# 5_2_switches.net
KiCad netlist of a schematic drawn in Altium Designer
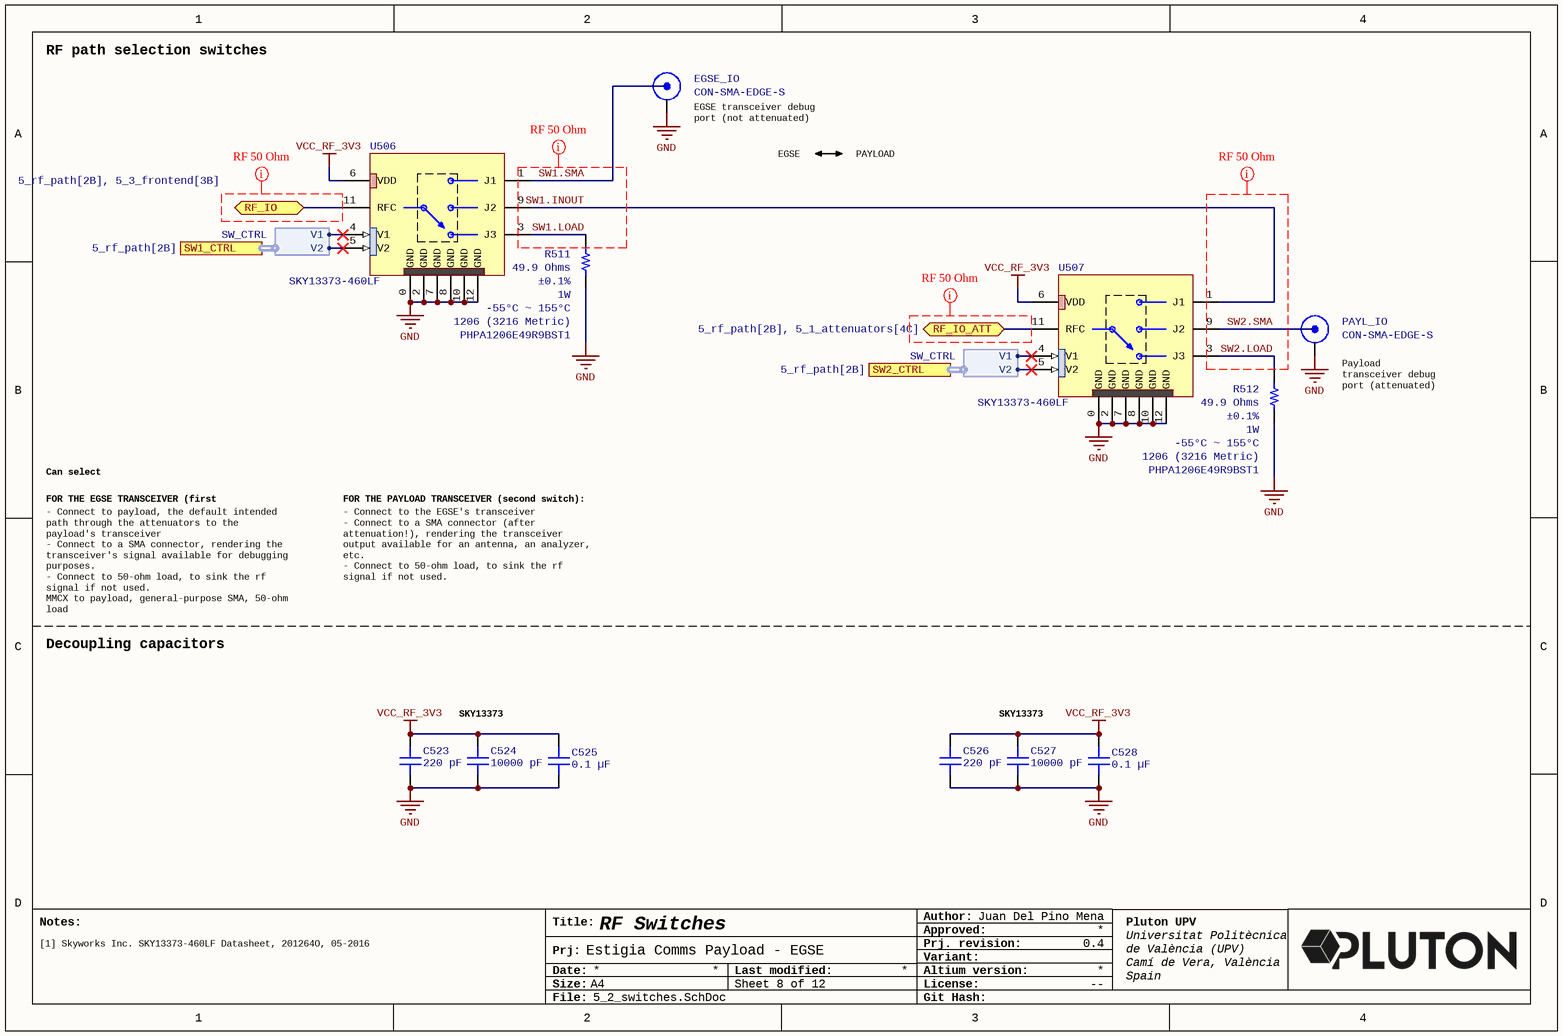
[diagram p0: 5_2_switches.SchDoc]

(export (version "E")
  (design (tool "Eeschema 10.0.6"))
  (components
    (comp (ref "C523")
      (value "220 pF")
      (footprint "CAP 0201_0603")
      (description "CAP CER 220PF 50V C0G/NP0 0201")
      (fields
        (field (name "PART NUMBER") "GRM0335C1H221JA01D")
        (field (name "MANUFACTURER") "Murata Electronics")
      )
      (libsource (lib "Celestial Altium Library - altium_library") (part "Capacitor"))
    )
    (comp (ref "C524")
      (value "10000 pF")
      (footprint "CAP 0402_1005")
      (description "CAP CER 10000PF 25V C0G/NP0 0402")
      (fields
        (field (name "PART NUMBER") "GRM1555C1E103JE01J")
        (field (name "MANUFACTURER") "Murata Electronics")
      )
      (libsource (lib "Celestial Altium Library - altium_library") (part "Capacitor"))
    )
    (comp (ref "C525")
      (value "0.1 µF")
      (footprint "CAP 0402_1005")
      (description "CAP CER 0402 0.1UF 16V X7R 10%")
      (fields (field (name "PART NUMBER") "C0402C104K4RECAUTO") (field (name "MANUFACTURER") "KEMET"))
      (libsource (lib "Celestial Altium Library - altium_library") (part "Capacitor"))
    )
    (comp (ref "C526")
      (value "220 pF")
      (footprint "CAP 0201_0603")
      (description "CAP CER 220PF 50V C0G/NP0 0201")
      (fields
        (field (name "PART NUMBER") "GRM0335C1H221JA01D")
        (field (name "MANUFACTURER") "Murata Electronics")
      )
      (libsource (lib "Celestial Altium Library - altium_library") (part "Capacitor"))
    )
    (comp (ref "C527")
      (value "10000 pF")
      (footprint "CAP 0402_1005")
      (description "CAP CER 10000PF 25V C0G/NP0 0402")
      (fields
        (field (name "PART NUMBER") "GRM1555C1E103JE01J")
        (field (name "MANUFACTURER") "Murata Electronics")
      )
      (libsource (lib "Celestial Altium Library - altium_library") (part "Capacitor"))
    )
    (comp (ref "C528")
      (value "0.1 µF")
      (footprint "CAP 0402_1005")
      (description "CAP CER 0402 0.1UF 16V X7R 10%")
      (fields (field (name "PART NUMBER") "C0402C104K4RECAUTO") (field (name "MANUFACTURER") "KEMET"))
      (libsource (lib "Celestial Altium Library - altium_library") (part "Capacitor"))
    )
    (comp (ref "EGSE_IO")
      (value "CON-SMA-EDGE-S")
      (footprint "connectors:CON-SMA-EDGE-S")
      (libsource (lib "connectors") (part "CON-SMA-EDGE-S"))
    )
    (comp (ref "PAYL_IO")
      (value "CON-SMA-EDGE-S")
      (footprint "connectors:CON-SMA-EDGE-S")
      (libsource (lib "connectors") (part "CON-SMA-EDGE-S"))
    )
    (comp (ref "R511")
      (value "49.9 Ohms")
      (footprint "RES 1206_3216")
      (description "THIN FILM RES SMD 49.9 OHM 0.1%")
      (fields
        (field (name "PART NUMBER") "PHPA1206E49R9BST1")
        (field (name "DEVICE PACKAGE") "1206 (3216 Metric)")
        (field (name "MANUFACTURER") "Vishay Dale Thin Film")
        (field (name "OPERATING TEMPERATURE") "-55°C ~ 155°C")
        (field (name "POWER (WATTS)") "1W")
        (field (name "TOLERANCE") "±0.1%")
      )
      (libsource (lib "Celestial Altium Library - altium_library") (part "Resistor"))
    )
    (comp (ref "R512")
      (value "49.9 Ohms")
      (footprint "RES 1206_3216")
      (description "THIN FILM RES SMD 49.9 OHM 0.1%")
      (fields
        (field (name "PART NUMBER") "PHPA1206E49R9BST1")
        (field (name "DEVICE PACKAGE") "1206 (3216 Metric)")
        (field (name "MANUFACTURER") "Vishay Dale Thin Film")
        (field (name "OPERATING TEMPERATURE") "-55°C ~ 155°C")
        (field (name "POWER (WATTS)") "1W")
        (field (name "TOLERANCE") "±0.1%")
      )
      (libsource (lib "Celestial Altium Library - altium_library") (part "Resistor"))
    )
    (comp (ref "U506")
      (value "SKY13373-460LF")
      (footprint "ics:SKY13373-460LF")
      (description "0.1 to 8.0 GHz SP3T Switch")
      (libsource (lib "rf") (part "SKY13373-460LF"))
    )
    (comp (ref "U507")
      (value "SKY13373-460LF")
      (footprint "ics:SKY13373-460LF")
      (description "0.1 to 8.0 GHz SP3T Switch")
      (libsource (lib "rf") (part "SKY13373-460LF"))
    )
  )
  (nets
    (net (code "2") (name "/RF_IO") (class "Default")
      (node (ref "U506") (pin "11") (pinfunction "RFC_11") (pintype "passive"))
    )
    (net (code "3") (name "/RF_IO_ATT") (class "Default")
      (node (ref "U507") (pin "11") (pinfunction "RFC_11") (pintype "passive"))
    )
    (net (code "4") (name "/SW1.INOUT") (class "Default")
      (node (ref "U506") (pin "9") (pinfunction "J2_9") (pintype "passive"))
      (node (ref "U507") (pin "1") (pinfunction "J1_1") (pintype "passive"))
    )
    (net (code "5") (name "/SW1.LOAD") (class "Default")
      (node (ref "R511") (pin "2") (pinfunction "2_2") (pintype "passive"))
      (node (ref "U506") (pin "3") (pinfunction "J3_3") (pintype "passive"))
    )
    (net (code "6") (name "/SW1.SMA") (class "Default")
      (node (ref "EGSE_IO") (pin "1") (pinfunction "SIGNAL_1") (pintype "passive"))
      (node (ref "U506") (pin "1") (pinfunction "J1_1") (pintype "passive"))
    )
    (net (code "7") (name "/SW2.LOAD") (class "Default")
      (node (ref "R512") (pin "2") (pinfunction "2_2") (pintype "passive"))
      (node (ref "U507") (pin "3") (pinfunction "J3_3") (pintype "passive"))
    )
    (net (code "8") (name "/SW2.SMA") (class "Default")
      (node (ref "PAYL_IO") (pin "1") (pinfunction "SIGNAL_1") (pintype "passive"))
      (node (ref "U507") (pin "9") (pinfunction "J2_9") (pintype "passive"))
    )
    (net (code "10") (name "GND") (class "Default")
      (node (ref "C523") (pin "1") (pinfunction "1_1") (pintype "passive"))
      (node (ref "C524") (pin "1") (pinfunction "1_1") (pintype "passive"))
      (node (ref "C525") (pin "1") (pinfunction "1_1") (pintype "passive"))
      (node (ref "C526") (pin "1") (pinfunction "1_1") (pintype "passive"))
      (node (ref "C527") (pin "1") (pinfunction "1_1") (pintype "passive"))
      (node (ref "C528") (pin "1") (pinfunction "1_1") (pintype "passive"))
      (node (ref "EGSE_IO") (pin "2") (pinfunction "GND_2") (pintype "passive"))
      (node (ref "PAYL_IO") (pin "2") (pinfunction "GND_2") (pintype "passive"))
      (node (ref "R511") (pin "1") (pinfunction "1_1") (pintype "passive"))
      (node (ref "R512") (pin "1") (pinfunction "1_1") (pintype "passive"))
      (node (ref "U506") (pin "0") (pinfunction "GND_0") (pintype "power_in"))
      (node (ref "U506") (pin "10") (pinfunction "GND_10") (pintype "power_in"))
      (node (ref "U506") (pin "12") (pinfunction "GND_12") (pintype "passive"))
      (node (ref "U506") (pin "2") (pinfunction "GND_2") (pintype "power_in"))
      (node (ref "U506") (pin "7") (pinfunction "GND_7") (pintype "power_in"))
      (node (ref "U506") (pin "8") (pinfunction "GND_8") (pintype "power_in"))
      (node (ref "U507") (pin "0") (pinfunction "GND_0") (pintype "power_in"))
      (node (ref "U507") (pin "10") (pinfunction "GND_10") (pintype "power_in"))
      (node (ref "U507") (pin "12") (pinfunction "GND_12") (pintype "passive"))
      (node (ref "U507") (pin "2") (pinfunction "GND_2") (pintype "power_in"))
      (node (ref "U507") (pin "7") (pinfunction "GND_7") (pintype "power_in"))
      (node (ref "U507") (pin "8") (pinfunction "GND_8") (pintype "power_in"))
    )
    (net (code "11") (name "VCC_RF_3V3") (class "Default")
      (node (ref "C523") (pin "2") (pinfunction "2_2") (pintype "passive"))
      (node (ref "C524") (pin "2") (pinfunction "2_2") (pintype "passive"))
      (node (ref "C525") (pin "2") (pinfunction "2_2") (pintype "passive"))
      (node (ref "C526") (pin "2") (pinfunction "2_2") (pintype "passive"))
      (node (ref "C527") (pin "2") (pinfunction "2_2") (pintype "passive"))
      (node (ref "C528") (pin "2") (pinfunction "2_2") (pintype "passive"))
      (node (ref "U506") (pin "6") (pinfunction "VDD_6") (pintype "power_in"))
      (node (ref "U507") (pin "6") (pinfunction "VDD_6") (pintype "power_in"))
    )
    (net (code "12") (name "unconnected-(U506-V1-Pad4)") (class "Default")
      (node (ref "U506") (pin "4") (pinfunction "V1_4") (pintype "input+no_connect"))
    )
    (net (code "13") (name "unconnected-(U506-V2-Pad5)") (class "Default")
      (node (ref "U506") (pin "5") (pinfunction "V2_5") (pintype "input+no_connect"))
    )
    (net (code "14") (name "unconnected-(U507-V1-Pad4)") (class "Default")
      (node (ref "U507") (pin "4") (pinfunction "V1_4") (pintype "input+no_connect"))
    )
    (net (code "15") (name "unconnected-(U507-V2-Pad5)") (class "Default")
      (node (ref "U507") (pin "5") (pinfunction "V2_5") (pintype "input+no_connect"))
    )
  )
)
